# piezo-layer_v0_3-R001.net
KiCad netlist of a schematic drawn in EAGLE
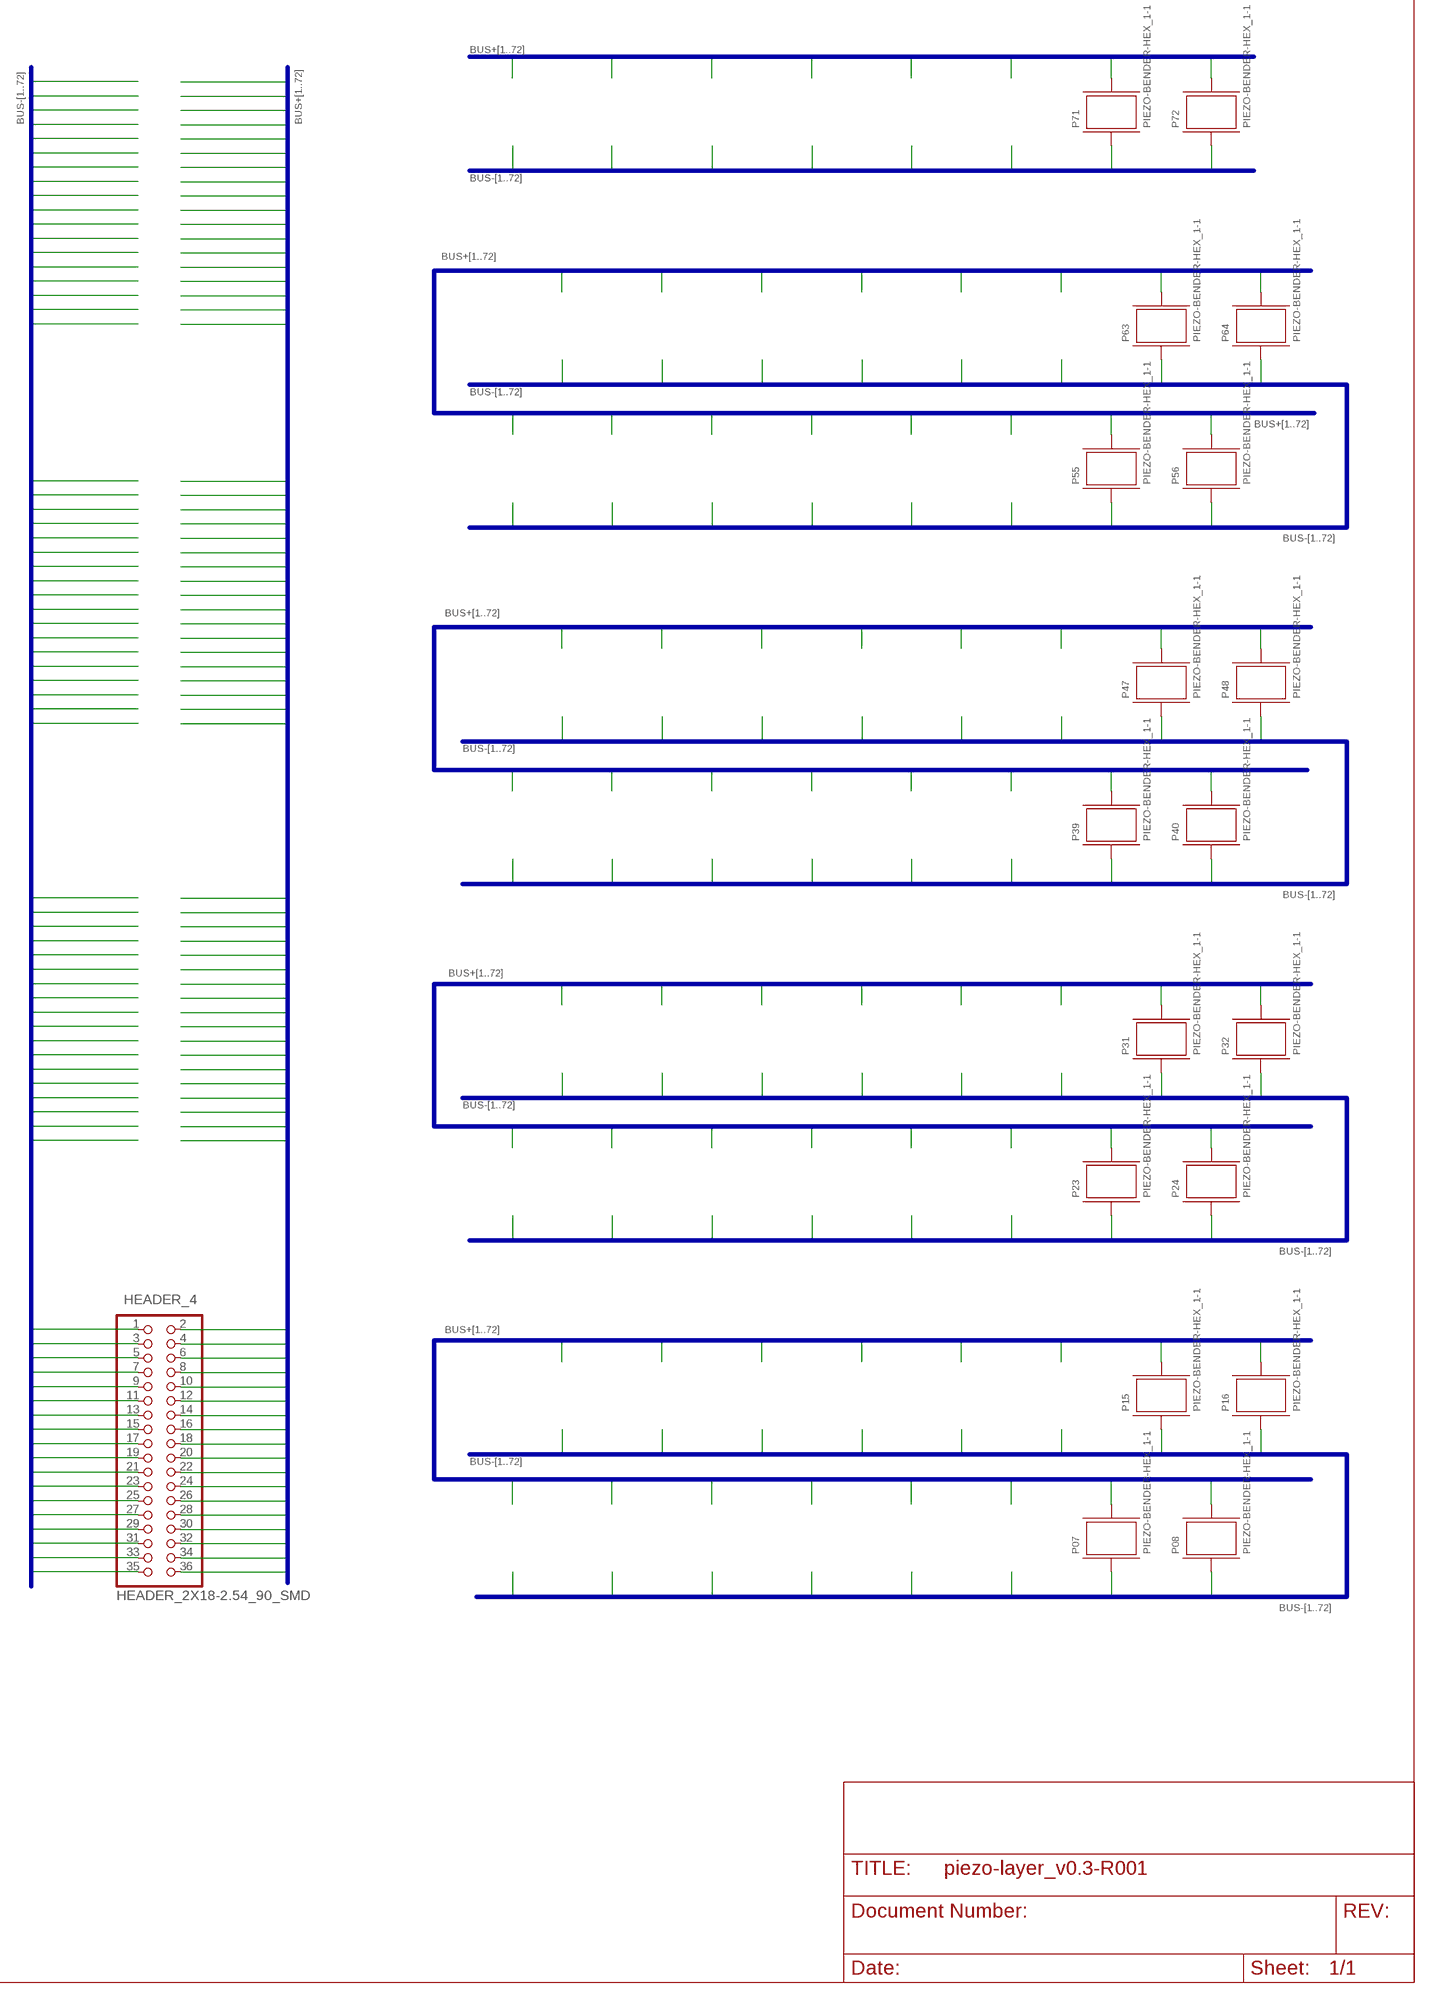
[diagram p0: schematic, sheet 1]

(export (version "E")
  (design (tool "Eeschema 10.0.6"))
  (components
    (comp (ref "HEADER_4")
      (value "HEADER_2X18-2.54_90_SMD")
      (footprint "eagle-import:2X18_2.54_90_SMD")
      (libsource (lib "eagle-import") (part "HEADER_2X18-2.54_90_SMD"))
    )
    (comp (ref "P07")
      (value "PIEZO-BENDER-HEX_1-1")
      (footprint "eagle-import:PIEZO-BENDER-HEX_16MM_1+_1-")
      (libsource (lib "eagle-import") (part "PIEZO-BENDER-HEX_1-1"))
    )
    (comp (ref "P08")
      (value "PIEZO-BENDER-HEX_1-1")
      (footprint "eagle-import:PIEZO-BENDER-HEX_16MM_1+_1-")
      (libsource (lib "eagle-import") (part "PIEZO-BENDER-HEX_1-1"))
    )
    (comp (ref "P15")
      (value "PIEZO-BENDER-HEX_1-1")
      (footprint "eagle-import:PIEZO-BENDER-HEX_16MM_1+_1-")
      (libsource (lib "eagle-import") (part "PIEZO-BENDER-HEX_1-1"))
    )
    (comp (ref "P16")
      (value "PIEZO-BENDER-HEX_1-1")
      (footprint "eagle-import:PIEZO-BENDER-HEX_16MM_1+_1-")
      (libsource (lib "eagle-import") (part "PIEZO-BENDER-HEX_1-1"))
    )
    (comp (ref "P23")
      (value "PIEZO-BENDER-HEX_1-1")
      (footprint "eagle-import:PIEZO-BENDER-HEX_16MM_1+_1-")
      (libsource (lib "eagle-import") (part "PIEZO-BENDER-HEX_1-1"))
    )
    (comp (ref "P24")
      (value "PIEZO-BENDER-HEX_1-1")
      (footprint "eagle-import:PIEZO-BENDER-HEX_16MM_1+_1-")
      (libsource (lib "eagle-import") (part "PIEZO-BENDER-HEX_1-1"))
    )
    (comp (ref "P31")
      (value "PIEZO-BENDER-HEX_1-1")
      (footprint "eagle-import:PIEZO-BENDER-HEX_16MM_1+_1-")
      (libsource (lib "eagle-import") (part "PIEZO-BENDER-HEX_1-1"))
    )
    (comp (ref "P32")
      (value "PIEZO-BENDER-HEX_1-1")
      (footprint "eagle-import:PIEZO-BENDER-HEX_16MM_1+_1-")
      (libsource (lib "eagle-import") (part "PIEZO-BENDER-HEX_1-1"))
    )
    (comp (ref "P39")
      (value "PIEZO-BENDER-HEX_1-1")
      (footprint "eagle-import:PIEZO-BENDER-HEX_16MM_1+_1-")
      (libsource (lib "eagle-import") (part "PIEZO-BENDER-HEX_1-1"))
    )
    (comp (ref "P40")
      (value "PIEZO-BENDER-HEX_1-1")
      (footprint "eagle-import:PIEZO-BENDER-HEX_16MM_1+_1-")
      (libsource (lib "eagle-import") (part "PIEZO-BENDER-HEX_1-1"))
    )
    (comp (ref "P47")
      (value "PIEZO-BENDER-HEX_1-1")
      (footprint "eagle-import:PIEZO-BENDER-HEX_16MM_1+_1-")
      (libsource (lib "eagle-import") (part "PIEZO-BENDER-HEX_1-1"))
    )
    (comp (ref "P48")
      (value "PIEZO-BENDER-HEX_1-1")
      (footprint "eagle-import:PIEZO-BENDER-HEX_16MM_1+_1-")
      (libsource (lib "eagle-import") (part "PIEZO-BENDER-HEX_1-1"))
    )
    (comp (ref "P55")
      (value "PIEZO-BENDER-HEX_1-1")
      (footprint "eagle-import:PIEZO-BENDER-HEX_16MM_1+_1-")
      (libsource (lib "eagle-import") (part "PIEZO-BENDER-HEX_1-1"))
    )
    (comp (ref "P56")
      (value "PIEZO-BENDER-HEX_1-1")
      (footprint "eagle-import:PIEZO-BENDER-HEX_16MM_1+_1-")
      (libsource (lib "eagle-import") (part "PIEZO-BENDER-HEX_1-1"))
    )
    (comp (ref "P63")
      (value "PIEZO-BENDER-HEX_1-1")
      (footprint "eagle-import:PIEZO-BENDER-HEX_16MM_1+_1-")
      (libsource (lib "eagle-import") (part "PIEZO-BENDER-HEX_1-1"))
    )
    (comp (ref "P64")
      (value "PIEZO-BENDER-HEX_1-1")
      (footprint "eagle-import:PIEZO-BENDER-HEX_16MM_1+_1-")
      (libsource (lib "eagle-import") (part "PIEZO-BENDER-HEX_1-1"))
    )
    (comp (ref "P71")
      (value "PIEZO-BENDER-HEX_1-1")
      (footprint "eagle-import:PIEZO-BENDER-HEX_16MM_1+_1-")
      (libsource (lib "eagle-import") (part "PIEZO-BENDER-HEX_1-1"))
    )
    (comp (ref "P72")
      (value "PIEZO-BENDER-HEX_1-1")
      (footprint "eagle-import:PIEZO-BENDER-HEX_16MM_1+_1-")
      (libsource (lib "eagle-import") (part "PIEZO-BENDER-HEX_1-1"))
    )
  )
  (nets
    (net (code "7") (name "/BUS+7") (class "Default")
      (node (ref "HEADER_4") (pin "18") (pinfunction "18_18") (pintype "passive"))
      (node (ref "P07") (pin "TIP1") (pinfunction "+_1_TIP1") (pintype "bidirectional"))
    )
    (net (code "8") (name "/BUS+8") (class "Default")
      (node (ref "HEADER_4") (pin "36") (pinfunction "36_36") (pintype "passive"))
      (node (ref "P08") (pin "TIP1") (pinfunction "+_1_TIP1") (pintype "bidirectional"))
    )
    (net (code "15") (name "/BUS+15") (class "Default")
      (node (ref "HEADER_4") (pin "16") (pinfunction "16_16") (pintype "passive"))
      (node (ref "P15") (pin "TIP1") (pinfunction "+_1_TIP1") (pintype "bidirectional"))
    )
    (net (code "16") (name "/BUS+16") (class "Default")
      (node (ref "HEADER_4") (pin "34") (pinfunction "34_34") (pintype "passive"))
      (node (ref "P16") (pin "TIP1") (pinfunction "+_1_TIP1") (pintype "bidirectional"))
    )
    (net (code "23") (name "/BUS+23") (class "Default")
      (node (ref "HEADER_4") (pin "14") (pinfunction "14_14") (pintype "passive"))
      (node (ref "P23") (pin "TIP1") (pinfunction "+_1_TIP1") (pintype "bidirectional"))
    )
    (net (code "24") (name "/BUS+24") (class "Default")
      (node (ref "HEADER_4") (pin "32") (pinfunction "32_32") (pintype "passive"))
      (node (ref "P24") (pin "TIP1") (pinfunction "+_1_TIP1") (pintype "bidirectional"))
    )
    (net (code "31") (name "/BUS+31") (class "Default")
      (node (ref "HEADER_4") (pin "12") (pinfunction "12_12") (pintype "passive"))
      (node (ref "P31") (pin "TIP1") (pinfunction "+_1_TIP1") (pintype "bidirectional"))
    )
    (net (code "32") (name "/BUS+32") (class "Default")
      (node (ref "HEADER_4") (pin "30") (pinfunction "30_30") (pintype "passive"))
      (node (ref "P32") (pin "TIP1") (pinfunction "+_1_TIP1") (pintype "bidirectional"))
    )
    (net (code "39") (name "/BUS+39") (class "Default")
      (node (ref "HEADER_4") (pin "10") (pinfunction "10_10") (pintype "passive"))
      (node (ref "P39") (pin "TIP1") (pinfunction "+_1_TIP1") (pintype "bidirectional"))
    )
    (net (code "40") (name "/BUS+40") (class "Default")
      (node (ref "HEADER_4") (pin "28") (pinfunction "28_28") (pintype "passive"))
      (node (ref "P40") (pin "TIP1") (pinfunction "+_1_TIP1") (pintype "bidirectional"))
    )
    (net (code "47") (name "/BUS+47") (class "Default")
      (node (ref "HEADER_4") (pin "8") (pinfunction "8_8") (pintype "passive"))
      (node (ref "P47") (pin "TIP1") (pinfunction "+_1_TIP1") (pintype "bidirectional"))
    )
    (net (code "48") (name "/BUS+48") (class "Default")
      (node (ref "HEADER_4") (pin "26") (pinfunction "26_26") (pintype "passive"))
      (node (ref "P48") (pin "TIP1") (pinfunction "+_1_TIP1") (pintype "bidirectional"))
    )
    (net (code "55") (name "/BUS+55") (class "Default")
      (node (ref "HEADER_4") (pin "6") (pinfunction "6_6") (pintype "passive"))
      (node (ref "P55") (pin "TIP1") (pinfunction "+_1_TIP1") (pintype "bidirectional"))
    )
    (net (code "56") (name "/BUS+56") (class "Default")
      (node (ref "HEADER_4") (pin "24") (pinfunction "24_24") (pintype "passive"))
      (node (ref "P56") (pin "TIP1") (pinfunction "+_1_TIP1") (pintype "bidirectional"))
    )
    (net (code "63") (name "/BUS+63") (class "Default")
      (node (ref "HEADER_4") (pin "4") (pinfunction "4_4") (pintype "passive"))
      (node (ref "P63") (pin "TIP1") (pinfunction "+_1_TIP1") (pintype "bidirectional"))
    )
    (net (code "64") (name "/BUS+64") (class "Default")
      (node (ref "HEADER_4") (pin "22") (pinfunction "22_22") (pintype "passive"))
      (node (ref "P64") (pin "TIP1") (pinfunction "+_1_TIP1") (pintype "bidirectional"))
    )
    (net (code "71") (name "/BUS+71") (class "Default")
      (node (ref "HEADER_4") (pin "2") (pinfunction "2_2") (pintype "passive"))
      (node (ref "P71") (pin "TIP1") (pinfunction "+_1_TIP1") (pintype "bidirectional"))
    )
    (net (code "72") (name "/BUS+72") (class "Default")
      (node (ref "HEADER_4") (pin "20") (pinfunction "20_20") (pintype "passive"))
      (node (ref "P72") (pin "TIP1") (pinfunction "+_1_TIP1") (pintype "bidirectional"))
    )
    (net (code "80") (name "/BUS-7") (class "Default")
      (node (ref "HEADER_4") (pin "17") (pinfunction "17_17") (pintype "passive"))
      (node (ref "P07") (pin "PAD1") (pinfunction "-_1_PAD1") (pintype "bidirectional"))
    )
    (net (code "81") (name "/BUS-8") (class "Default")
      (node (ref "HEADER_4") (pin "35") (pinfunction "35_35") (pintype "passive"))
      (node (ref "P08") (pin "PAD1") (pinfunction "-_1_PAD1") (pintype "bidirectional"))
    )
    (net (code "88") (name "/BUS-15") (class "Default")
      (node (ref "HEADER_4") (pin "15") (pinfunction "15_15") (pintype "passive"))
      (node (ref "P15") (pin "PAD1") (pinfunction "-_1_PAD1") (pintype "bidirectional"))
    )
    (net (code "89") (name "/BUS-16") (class "Default")
      (node (ref "HEADER_4") (pin "33") (pinfunction "33_33") (pintype "passive"))
      (node (ref "P16") (pin "PAD1") (pinfunction "-_1_PAD1") (pintype "bidirectional"))
    )
    (net (code "96") (name "/BUS-23") (class "Default")
      (node (ref "HEADER_4") (pin "13") (pinfunction "13_13") (pintype "passive"))
      (node (ref "P23") (pin "PAD1") (pinfunction "-_1_PAD1") (pintype "bidirectional"))
    )
    (net (code "97") (name "/BUS-24") (class "Default")
      (node (ref "HEADER_4") (pin "31") (pinfunction "31_31") (pintype "passive"))
      (node (ref "P24") (pin "PAD1") (pinfunction "-_1_PAD1") (pintype "bidirectional"))
    )
    (net (code "104") (name "/BUS-31") (class "Default")
      (node (ref "HEADER_4") (pin "11") (pinfunction "11_11") (pintype "passive"))
      (node (ref "P31") (pin "PAD1") (pinfunction "-_1_PAD1") (pintype "bidirectional"))
    )
    (net (code "105") (name "/BUS-32") (class "Default")
      (node (ref "HEADER_4") (pin "29") (pinfunction "29_29") (pintype "passive"))
      (node (ref "P32") (pin "PAD1") (pinfunction "-_1_PAD1") (pintype "bidirectional"))
    )
    (net (code "112") (name "/BUS-39") (class "Default")
      (node (ref "HEADER_4") (pin "9") (pinfunction "9_9") (pintype "passive"))
      (node (ref "P39") (pin "PAD1") (pinfunction "-_1_PAD1") (pintype "bidirectional"))
    )
    (net (code "113") (name "/BUS-40") (class "Default")
      (node (ref "HEADER_4") (pin "27") (pinfunction "27_27") (pintype "passive"))
      (node (ref "P40") (pin "PAD1") (pinfunction "-_1_PAD1") (pintype "bidirectional"))
    )
    (net (code "120") (name "/BUS-47") (class "Default")
      (node (ref "HEADER_4") (pin "7") (pinfunction "7_7") (pintype "passive"))
      (node (ref "P47") (pin "PAD1") (pinfunction "-_1_PAD1") (pintype "bidirectional"))
    )
    (net (code "121") (name "/BUS-48") (class "Default")
      (node (ref "HEADER_4") (pin "25") (pinfunction "25_25") (pintype "passive"))
      (node (ref "P48") (pin "PAD1") (pinfunction "-_1_PAD1") (pintype "bidirectional"))
    )
    (net (code "128") (name "/BUS-55") (class "Default")
      (node (ref "HEADER_4") (pin "5") (pinfunction "5_5") (pintype "passive"))
      (node (ref "P55") (pin "PAD1") (pinfunction "-_1_PAD1") (pintype "bidirectional"))
    )
    (net (code "129") (name "/BUS-56") (class "Default")
      (node (ref "HEADER_4") (pin "23") (pinfunction "23_23") (pintype "passive"))
      (node (ref "P56") (pin "PAD1") (pinfunction "-_1_PAD1") (pintype "bidirectional"))
    )
    (net (code "136") (name "/BUS-63") (class "Default")
      (node (ref "HEADER_4") (pin "3") (pinfunction "3_3") (pintype "passive"))
      (node (ref "P63") (pin "PAD1") (pinfunction "-_1_PAD1") (pintype "bidirectional"))
    )
    (net (code "137") (name "/BUS-64") (class "Default")
      (node (ref "HEADER_4") (pin "21") (pinfunction "21_21") (pintype "passive"))
      (node (ref "P64") (pin "PAD1") (pinfunction "-_1_PAD1") (pintype "bidirectional"))
    )
    (net (code "144") (name "/BUS-71") (class "Default")
      (node (ref "HEADER_4") (pin "1") (pinfunction "1_1") (pintype "passive"))
      (node (ref "P71") (pin "PAD1") (pinfunction "-_1_PAD1") (pintype "bidirectional"))
    )
    (net (code "145") (name "/BUS-72") (class "Default")
      (node (ref "HEADER_4") (pin "19") (pinfunction "19_19") (pintype "passive"))
      (node (ref "P72") (pin "PAD1") (pinfunction "-_1_PAD1") (pintype "bidirectional"))
    )
  )
)
